# display_driver.net
KiCad netlist of a schematic drawn in EAGLE
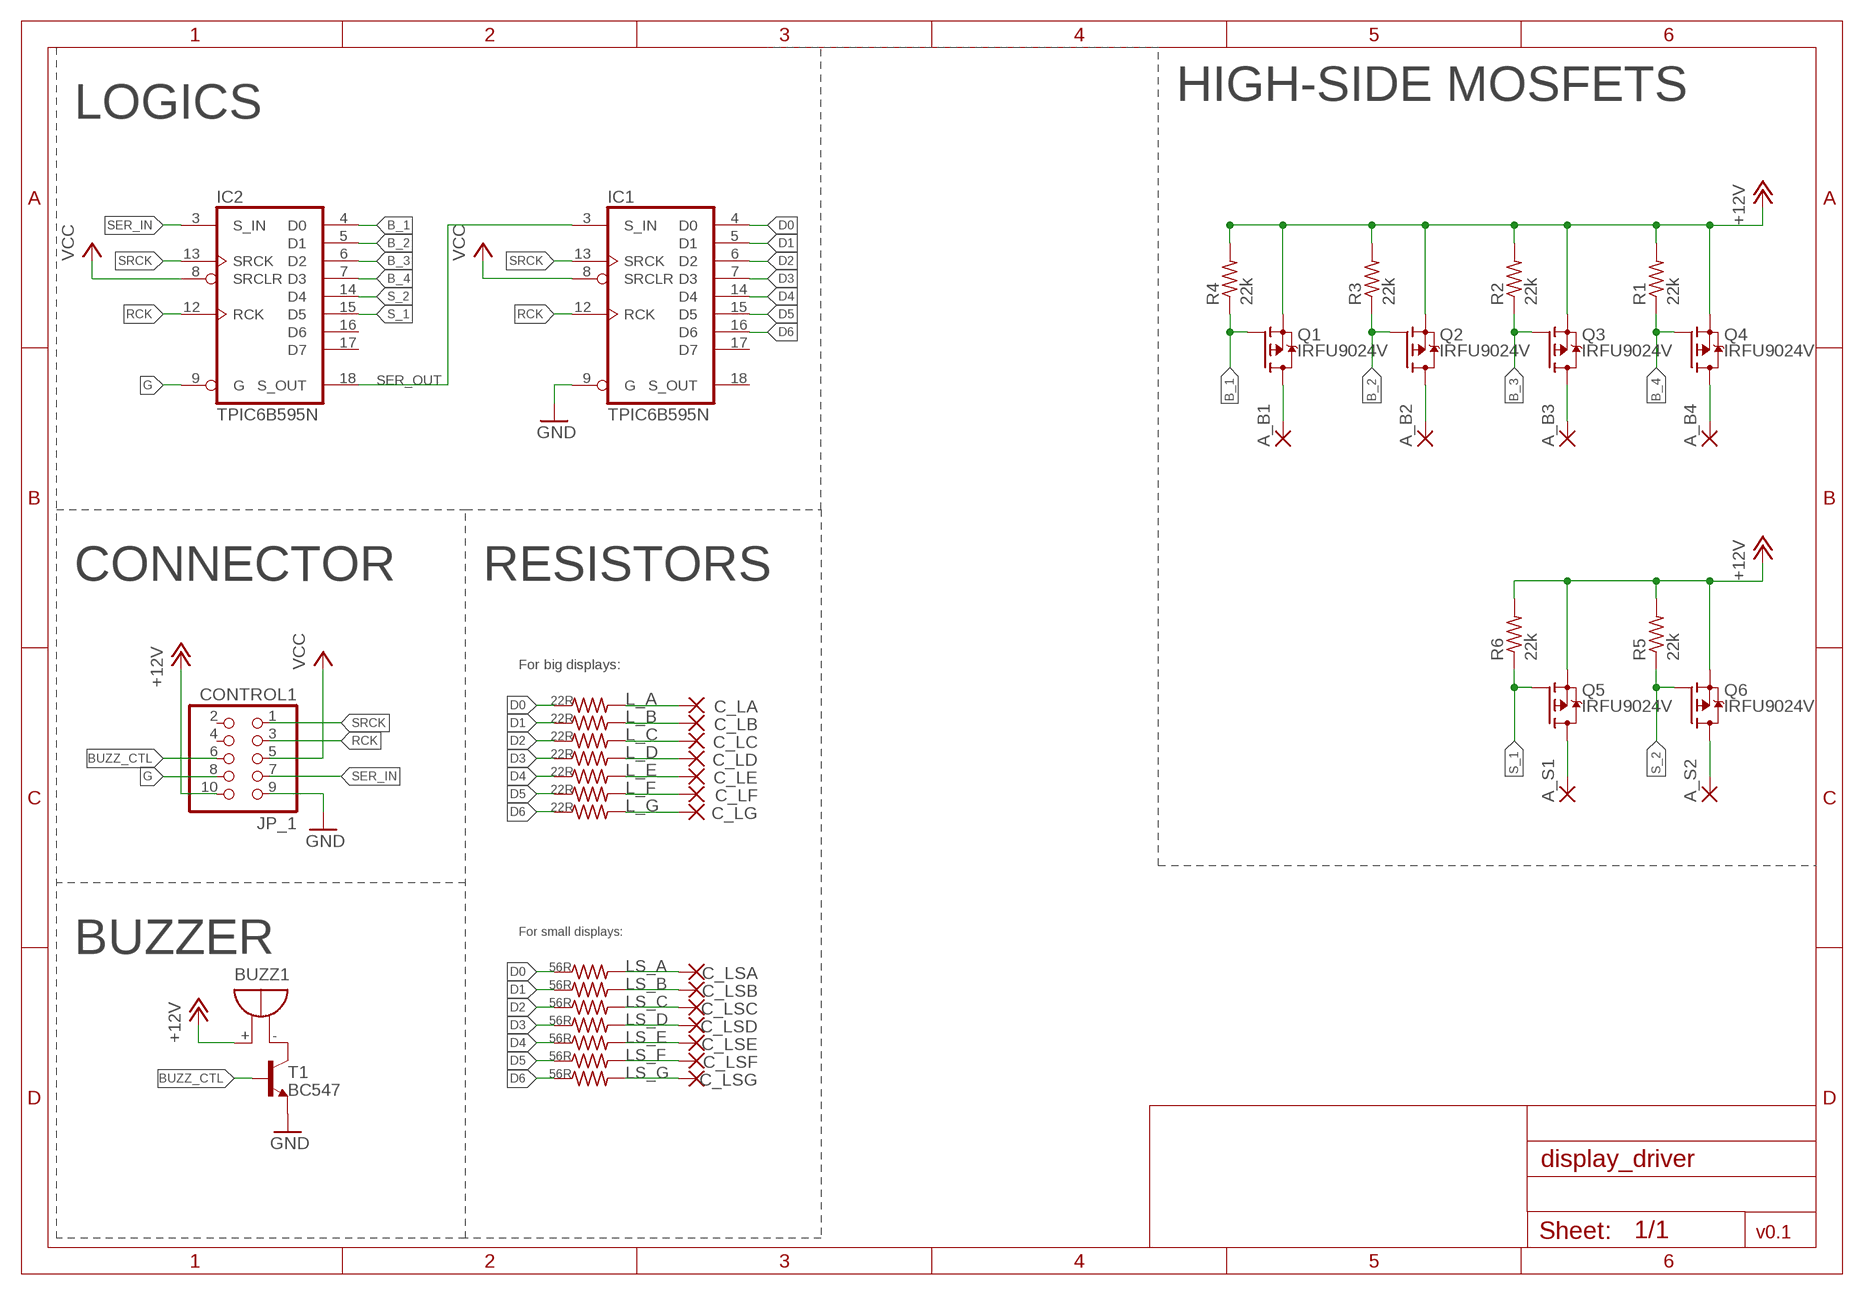
[diagram p0: schematic, sheet 1]

(export (version "E")
  (design (tool "Eeschema 10.0.6"))
  (components
    (comp (ref "A_B1")
      (value "1,6/0,9")
      (footprint "eagle-import:1,6_0,9")
      (libsource (lib "eagle-import") (part "1,6/0,9"))
    )
    (comp (ref "A_B2")
      (value "1,6/0,9")
      (footprint "eagle-import:1,6_0,9")
      (libsource (lib "eagle-import") (part "1,6/0,9"))
    )
    (comp (ref "A_B3")
      (value "1,6/0,9")
      (footprint "eagle-import:1,6_0,9")
      (libsource (lib "eagle-import") (part "1,6/0,9"))
    )
    (comp (ref "A_B4")
      (value "1,6/0,9")
      (footprint "eagle-import:1,6_0,9")
      (libsource (lib "eagle-import") (part "1,6/0,9"))
    )
    (comp (ref "A_S1")
      (value "1,6/0,9")
      (footprint "eagle-import:1,6_0,9")
      (libsource (lib "eagle-import") (part "1,6/0,9"))
    )
    (comp (ref "A_S2")
      (value "1,6/0,9")
      (footprint "eagle-import:1,6_0,9")
      (libsource (lib "eagle-import") (part "1,6/0,9"))
    )
    (comp (ref "BUZZ1")
      (value "F/BC40")
      (footprint "eagle-import:F_BC40")
      (libsource (lib "eagle-import") (part "F/BC40"))
    )
    (comp (ref "CONTROL1")
      (value "JP_1")
      (footprint "eagle-import:2X05")
      (libsource (lib "eagle-import") (part "PINHD-2X5"))
    )
    (comp (ref "C_LA")
      (value "1,6/0,9")
      (footprint "eagle-import:1,6_0,9")
      (libsource (lib "eagle-import") (part "1,6/0,9"))
    )
    (comp (ref "C_LB")
      (value "1,6/0,9")
      (footprint "eagle-import:1,6_0,9")
      (libsource (lib "eagle-import") (part "1,6/0,9"))
    )
    (comp (ref "C_LC")
      (value "1,6/0,9")
      (footprint "eagle-import:1,6_0,9")
      (libsource (lib "eagle-import") (part "1,6/0,9"))
    )
    (comp (ref "C_LD")
      (value "1,6/0,9")
      (footprint "eagle-import:1,6_0,9")
      (libsource (lib "eagle-import") (part "1,6/0,9"))
    )
    (comp (ref "C_LE")
      (value "1,6/0,9")
      (footprint "eagle-import:1,6_0,9")
      (libsource (lib "eagle-import") (part "1,6/0,9"))
    )
    (comp (ref "C_LF")
      (value "1,6/0,9")
      (footprint "eagle-import:1,6_0,9")
      (libsource (lib "eagle-import") (part "1,6/0,9"))
    )
    (comp (ref "C_LG")
      (value "1,6/0,9")
      (footprint "eagle-import:1,6_0,9")
      (libsource (lib "eagle-import") (part "1,6/0,9"))
    )
    (comp (ref "C_LSA")
      (value "1,6/0,9")
      (footprint "eagle-import:1,6_0,9")
      (libsource (lib "eagle-import") (part "1,6/0,9"))
    )
    (comp (ref "C_LSB")
      (value "1,6/0,9")
      (footprint "eagle-import:1,6_0,9")
      (libsource (lib "eagle-import") (part "1,6/0,9"))
    )
    (comp (ref "C_LSC")
      (value "1,6/0,9")
      (footprint "eagle-import:1,6_0,9")
      (libsource (lib "eagle-import") (part "1,6/0,9"))
    )
    (comp (ref "C_LSD")
      (value "1,6/0,9")
      (footprint "eagle-import:1,6_0,9")
      (libsource (lib "eagle-import") (part "1,6/0,9"))
    )
    (comp (ref "C_LSE")
      (value "1,6/0,9")
      (footprint "eagle-import:1,6_0,9")
      (libsource (lib "eagle-import") (part "1,6/0,9"))
    )
    (comp (ref "C_LSF")
      (value "1,6/0,9")
      (footprint "eagle-import:1,6_0,9")
      (libsource (lib "eagle-import") (part "1,6/0,9"))
    )
    (comp (ref "C_LSG")
      (value "1,6/0,9")
      (footprint "eagle-import:1,6_0,9")
      (libsource (lib "eagle-import") (part "1,6/0,9"))
    )
    (comp (ref "IC1")
      (value "TPIC6B595N")
      (footprint "eagle-import:DIL20")
      (libsource (lib "eagle-import") (part "TPIC6B595N"))
    )
    (comp (ref "IC2")
      (value "TPIC6B595N")
      (footprint "eagle-import:DIL20")
      (libsource (lib "eagle-import") (part "TPIC6B595N"))
    )
    (comp (ref "Q1")
      (value "IRFU9024V")
      (footprint "eagle-import:TO251AA-V")
      (libsource (lib "eagle-import") (part "IRFU9024V"))
    )
    (comp (ref "Q2")
      (value "IRFU9024V")
      (footprint "eagle-import:TO251AA-V")
      (libsource (lib "eagle-import") (part "IRFU9024V"))
    )
    (comp (ref "Q3")
      (value "IRFU9024V")
      (footprint "eagle-import:TO251AA-V")
      (libsource (lib "eagle-import") (part "IRFU9024V"))
    )
    (comp (ref "Q4")
      (value "IRFU9024V")
      (footprint "eagle-import:TO251AA-V")
      (libsource (lib "eagle-import") (part "IRFU9024V"))
    )
    (comp (ref "Q5")
      (value "IRFU9024V")
      (footprint "eagle-import:TO251AA-V")
      (libsource (lib "eagle-import") (part "IRFU9024V"))
    )
    (comp (ref "Q6")
      (value "IRFU9024V")
      (footprint "eagle-import:TO251AA-V")
      (libsource (lib "eagle-import") (part "IRFU9024V"))
    )
    (comp (ref "R1")
      (value "22k")
      (footprint "eagle-import:0204_5")
      (libsource (lib "eagle-import") (part "R-US_0204/5"))
    )
    (comp (ref "R2")
      (value "22k")
      (footprint "eagle-import:0204_5")
      (libsource (lib "eagle-import") (part "R-US_0204/5"))
    )
    (comp (ref "R3")
      (value "22k")
      (footprint "eagle-import:0204_5")
      (libsource (lib "eagle-import") (part "R-US_0204/5"))
    )
    (comp (ref "R4")
      (value "22k")
      (footprint "eagle-import:0204_5")
      (libsource (lib "eagle-import") (part "R-US_0204/5"))
    )
    (comp (ref "R5")
      (value "22k")
      (footprint "eagle-import:0204_5")
      (libsource (lib "eagle-import") (part "R-US_0204/5"))
    )
    (comp (ref "R6")
      (value "22k")
      (footprint "eagle-import:0204_5")
      (libsource (lib "eagle-import") (part "R-US_0204/5"))
    )
    (comp (ref "R7")
      (value "22R")
      (footprint "eagle-import:0207_12")
      (libsource (lib "eagle-import") (part "R-US_0207/12"))
    )
    (comp (ref "R8")
      (value "22R")
      (footprint "eagle-import:0207_12")
      (libsource (lib "eagle-import") (part "R-US_0207/12"))
    )
    (comp (ref "R9")
      (value "22R")
      (footprint "eagle-import:0207_12")
      (libsource (lib "eagle-import") (part "R-US_0207/12"))
    )
    (comp (ref "R10")
      (value "22R")
      (footprint "eagle-import:0207_12")
      (libsource (lib "eagle-import") (part "R-US_0207/12"))
    )
    (comp (ref "R11")
      (value "22R")
      (footprint "eagle-import:0207_12")
      (libsource (lib "eagle-import") (part "R-US_0207/12"))
    )
    (comp (ref "R12")
      (value "22R")
      (footprint "eagle-import:0207_12")
      (libsource (lib "eagle-import") (part "R-US_0207/12"))
    )
    (comp (ref "R13")
      (value "22R")
      (footprint "eagle-import:0207_12")
      (libsource (lib "eagle-import") (part "R-US_0207/12"))
    )
    (comp (ref "R14")
      (value "56R")
      (footprint "eagle-import:0207_10")
      (libsource (lib "eagle-import") (part "R-US_0207/10"))
    )
    (comp (ref "R15")
      (value "56R")
      (footprint "eagle-import:0207_10")
      (libsource (lib "eagle-import") (part "R-US_0207/10"))
    )
    (comp (ref "R16")
      (value "56R")
      (footprint "eagle-import:0207_10")
      (libsource (lib "eagle-import") (part "R-US_0207/10"))
    )
    (comp (ref "R17")
      (value "56R")
      (footprint "eagle-import:0207_10")
      (libsource (lib "eagle-import") (part "R-US_0207/10"))
    )
    (comp (ref "R18")
      (value "56R")
      (footprint "eagle-import:0207_10")
      (libsource (lib "eagle-import") (part "R-US_0207/10"))
    )
    (comp (ref "R19")
      (value "56R")
      (footprint "eagle-import:0207_10")
      (libsource (lib "eagle-import") (part "R-US_0207/10"))
    )
    (comp (ref "R20")
      (value "56R")
      (footprint "eagle-import:0207_10")
      (libsource (lib "eagle-import") (part "R-US_0207/10"))
    )
    (comp (ref "T1")
      (value "BC547")
      (footprint "eagle-import:TO92")
      (libsource (lib "eagle-import") (part "BC547"))
    )
  )
  (nets
    (net (code "1") (name "+12V") (class "Default")
      (node (ref "BUZZ1") (pin "+") (pinfunction "+_+") (pintype "passive"))
      (node (ref "CONTROL1") (pin "10") (pinfunction "10_10") (pintype "passive"))
      (node (ref "Q1") (pin "3") (pinfunction "S_3") (pintype "passive"))
      (node (ref "Q2") (pin "3") (pinfunction "S_3") (pintype "passive"))
      (node (ref "Q3") (pin "3") (pinfunction "S_3") (pintype "passive"))
      (node (ref "Q4") (pin "3") (pinfunction "S_3") (pintype "passive"))
      (node (ref "Q5") (pin "3") (pinfunction "S_3") (pintype "passive"))
      (node (ref "Q6") (pin "3") (pinfunction "S_3") (pintype "passive"))
      (node (ref "R1") (pin "2") (pinfunction "2_2") (pintype "passive"))
      (node (ref "R2") (pin "2") (pinfunction "2_2") (pintype "passive"))
      (node (ref "R3") (pin "2") (pinfunction "2_2") (pintype "passive"))
      (node (ref "R4") (pin "2") (pinfunction "2_2") (pintype "passive"))
      (node (ref "R5") (pin "2") (pinfunction "2_2") (pintype "passive"))
      (node (ref "R6") (pin "2") (pinfunction "2_2") (pintype "passive"))
    )
    (net (code "2") (name "/LS_A") (class "Default")
      (node (ref "C_LSA") (pin "1") (pinfunction "P_1") (pintype "passive"))
      (node (ref "R14") (pin "2") (pinfunction "2_2") (pintype "passive"))
    )
    (net (code "3") (name "/LS_B") (class "Default")
      (node (ref "C_LSB") (pin "1") (pinfunction "P_1") (pintype "passive"))
      (node (ref "R15") (pin "2") (pinfunction "2_2") (pintype "passive"))
    )
    (net (code "4") (name "/LS_C") (class "Default")
      (node (ref "C_LSC") (pin "1") (pinfunction "P_1") (pintype "passive"))
      (node (ref "R16") (pin "2") (pinfunction "2_2") (pintype "passive"))
    )
    (net (code "5") (name "/LS_D") (class "Default")
      (node (ref "C_LSD") (pin "1") (pinfunction "P_1") (pintype "passive"))
      (node (ref "R17") (pin "2") (pinfunction "2_2") (pintype "passive"))
    )
    (net (code "6") (name "/LS_E") (class "Default")
      (node (ref "C_LSE") (pin "1") (pinfunction "P_1") (pintype "passive"))
      (node (ref "R18") (pin "2") (pinfunction "2_2") (pintype "passive"))
    )
    (net (code "7") (name "/LS_F") (class "Default")
      (node (ref "C_LSF") (pin "1") (pinfunction "P_1") (pintype "passive"))
      (node (ref "R19") (pin "2") (pinfunction "2_2") (pintype "passive"))
    )
    (net (code "8") (name "/LS_G") (class "Default")
      (node (ref "C_LSG") (pin "1") (pinfunction "P_1") (pintype "passive"))
      (node (ref "R20") (pin "2") (pinfunction "2_2") (pintype "passive"))
    )
    (net (code "9") (name "/L_A") (class "Default")
      (node (ref "C_LA") (pin "1") (pinfunction "P_1") (pintype "passive"))
      (node (ref "R7") (pin "2") (pinfunction "2_2") (pintype "passive"))
    )
    (net (code "10") (name "/L_B") (class "Default")
      (node (ref "C_LB") (pin "1") (pinfunction "P_1") (pintype "passive"))
      (node (ref "R8") (pin "2") (pinfunction "2_2") (pintype "passive"))
    )
    (net (code "11") (name "/L_C") (class "Default")
      (node (ref "C_LC") (pin "1") (pinfunction "P_1") (pintype "passive"))
      (node (ref "R9") (pin "2") (pinfunction "2_2") (pintype "passive"))
    )
    (net (code "12") (name "/L_D") (class "Default")
      (node (ref "C_LD") (pin "1") (pinfunction "P_1") (pintype "passive"))
      (node (ref "R10") (pin "2") (pinfunction "2_2") (pintype "passive"))
    )
    (net (code "13") (name "/L_E") (class "Default")
      (node (ref "C_LE") (pin "1") (pinfunction "P_1") (pintype "passive"))
      (node (ref "R11") (pin "2") (pinfunction "2_2") (pintype "passive"))
    )
    (net (code "14") (name "/L_F") (class "Default")
      (node (ref "C_LF") (pin "1") (pinfunction "P_1") (pintype "passive"))
      (node (ref "R12") (pin "2") (pinfunction "2_2") (pintype "passive"))
    )
    (net (code "15") (name "/L_G") (class "Default")
      (node (ref "C_LG") (pin "1") (pinfunction "P_1") (pintype "passive"))
      (node (ref "R13") (pin "2") (pinfunction "2_2") (pintype "passive"))
    )
    (net (code "16") (name "/SER_OUT") (class "Default")
      (node (ref "IC1") (pin "3") (pinfunction "S_IN_3") (pintype "input"))
      (node (ref "IC2") (pin "18") (pinfunction "S_OUT_18") (pintype "tri_state"))
    )
    (net (code "17") (name "BUZZ_CTL") (class "Default")
      (node (ref "CONTROL1") (pin "6") (pinfunction "6_6") (pintype "passive"))
      (node (ref "T1") (pin "2") (pinfunction "B_2") (pintype "passive"))
    )
    (net (code "18") (name "B_1") (class "Default")
      (node (ref "IC2") (pin "4") (pinfunction "D0_4") (pintype "tri_state"))
      (node (ref "Q1") (pin "1") (pinfunction "G_1") (pintype "passive"))
      (node (ref "R4") (pin "1") (pinfunction "1_1") (pintype "passive"))
    )
    (net (code "19") (name "B_2") (class "Default")
      (node (ref "IC2") (pin "5") (pinfunction "D1_5") (pintype "tri_state"))
      (node (ref "Q2") (pin "1") (pinfunction "G_1") (pintype "passive"))
      (node (ref "R3") (pin "1") (pinfunction "1_1") (pintype "passive"))
    )
    (net (code "20") (name "B_3") (class "Default")
      (node (ref "IC2") (pin "6") (pinfunction "D2_6") (pintype "tri_state"))
      (node (ref "Q3") (pin "1") (pinfunction "G_1") (pintype "passive"))
      (node (ref "R2") (pin "1") (pinfunction "1_1") (pintype "passive"))
    )
    (net (code "21") (name "B_4") (class "Default")
      (node (ref "IC2") (pin "7") (pinfunction "D3_7") (pintype "tri_state"))
      (node (ref "Q4") (pin "1") (pinfunction "G_1") (pintype "passive"))
      (node (ref "R1") (pin "1") (pinfunction "1_1") (pintype "passive"))
    )
    (net (code "22") (name "D0") (class "Default")
      (node (ref "IC1") (pin "4") (pinfunction "D0_4") (pintype "tri_state"))
      (node (ref "R14") (pin "1") (pinfunction "1_1") (pintype "passive"))
      (node (ref "R7") (pin "1") (pinfunction "1_1") (pintype "passive"))
    )
    (net (code "23") (name "D1") (class "Default")
      (node (ref "IC1") (pin "5") (pinfunction "D1_5") (pintype "tri_state"))
      (node (ref "R15") (pin "1") (pinfunction "1_1") (pintype "passive"))
      (node (ref "R8") (pin "1") (pinfunction "1_1") (pintype "passive"))
    )
    (net (code "24") (name "D2") (class "Default")
      (node (ref "IC1") (pin "6") (pinfunction "D2_6") (pintype "tri_state"))
      (node (ref "R16") (pin "1") (pinfunction "1_1") (pintype "passive"))
      (node (ref "R9") (pin "1") (pinfunction "1_1") (pintype "passive"))
    )
    (net (code "25") (name "D3") (class "Default")
      (node (ref "IC1") (pin "7") (pinfunction "D3_7") (pintype "tri_state"))
      (node (ref "R10") (pin "1") (pinfunction "1_1") (pintype "passive"))
      (node (ref "R17") (pin "1") (pinfunction "1_1") (pintype "passive"))
    )
    (net (code "26") (name "D4") (class "Default")
      (node (ref "IC1") (pin "14") (pinfunction "D4_14") (pintype "tri_state"))
      (node (ref "R11") (pin "1") (pinfunction "1_1") (pintype "passive"))
      (node (ref "R18") (pin "1") (pinfunction "1_1") (pintype "passive"))
    )
    (net (code "27") (name "D5") (class "Default")
      (node (ref "IC1") (pin "15") (pinfunction "D5_15") (pintype "tri_state"))
      (node (ref "R12") (pin "1") (pinfunction "1_1") (pintype "passive"))
      (node (ref "R19") (pin "1") (pinfunction "1_1") (pintype "passive"))
    )
    (net (code "28") (name "D6") (class "Default")
      (node (ref "IC1") (pin "16") (pinfunction "D6_16") (pintype "tri_state"))
      (node (ref "R13") (pin "1") (pinfunction "1_1") (pintype "passive"))
      (node (ref "R20") (pin "1") (pinfunction "1_1") (pintype "passive"))
    )
    (net (code "29") (name "G") (class "Default")
      (node (ref "CONTROL1") (pin "8") (pinfunction "8_8") (pintype "passive"))
      (node (ref "IC2") (pin "9") (pinfunction "G_9") (pintype "input"))
    )
    (net (code "30") (name "GND") (class "Default")
      (node (ref "CONTROL1") (pin "9") (pinfunction "9_9") (pintype "passive"))
      (node (ref "IC1") (pin "9") (pinfunction "G_9") (pintype "input"))
      (node (ref "T1") (pin "1") (pinfunction "E_1") (pintype "passive"))
    )
    (net (code "31") (name "Net-(A_B1-P)") (class "Default")
      (node (ref "A_B1") (pin "1") (pinfunction "P_1") (pintype "passive"))
      (node (ref "Q1") (pin "2") (pinfunction "D_2") (pintype "passive"))
    )
    (net (code "32") (name "Net-(A_B2-P)") (class "Default")
      (node (ref "A_B2") (pin "1") (pinfunction "P_1") (pintype "passive"))
      (node (ref "Q2") (pin "2") (pinfunction "D_2") (pintype "passive"))
    )
    (net (code "33") (name "Net-(A_B3-P)") (class "Default")
      (node (ref "A_B3") (pin "1") (pinfunction "P_1") (pintype "passive"))
      (node (ref "Q3") (pin "2") (pinfunction "D_2") (pintype "passive"))
    )
    (net (code "34") (name "Net-(A_B4-P)") (class "Default")
      (node (ref "A_B4") (pin "1") (pinfunction "P_1") (pintype "passive"))
      (node (ref "Q4") (pin "2") (pinfunction "D_2") (pintype "passive"))
    )
    (net (code "35") (name "Net-(A_S1-P)") (class "Default")
      (node (ref "A_S1") (pin "1") (pinfunction "P_1") (pintype "passive"))
      (node (ref "Q5") (pin "2") (pinfunction "D_2") (pintype "passive"))
    )
    (net (code "36") (name "Net-(A_S2-P)") (class "Default")
      (node (ref "A_S2") (pin "1") (pinfunction "P_1") (pintype "passive"))
      (node (ref "Q6") (pin "2") (pinfunction "D_2") (pintype "passive"))
    )
    (net (code "37") (name "Net-(T1-C)") (class "Default")
      (node (ref "BUZZ1") (pin "-") (pinfunction "-_-") (pintype "passive"))
      (node (ref "T1") (pin "3") (pinfunction "C_3") (pintype "passive"))
    )
    (net (code "38") (name "RCK") (class "Default")
      (node (ref "CONTROL1") (pin "3") (pinfunction "3_3") (pintype "passive"))
      (node (ref "IC1") (pin "12") (pinfunction "RCK_12") (pintype "input"))
      (node (ref "IC2") (pin "12") (pinfunction "RCK_12") (pintype "input"))
    )
    (net (code "39") (name "SER_IN") (class "Default")
      (node (ref "CONTROL1") (pin "7") (pinfunction "7_7") (pintype "passive"))
      (node (ref "IC2") (pin "3") (pinfunction "S_IN_3") (pintype "input"))
    )
    (net (code "40") (name "SRCK") (class "Default")
      (node (ref "CONTROL1") (pin "1") (pinfunction "1_1") (pintype "passive"))
      (node (ref "IC1") (pin "13") (pinfunction "SRCK_13") (pintype "input"))
      (node (ref "IC2") (pin "13") (pinfunction "SRCK_13") (pintype "input"))
    )
    (net (code "41") (name "S_1") (class "Default")
      (node (ref "IC2") (pin "15") (pinfunction "D5_15") (pintype "tri_state"))
      (node (ref "Q5") (pin "1") (pinfunction "G_1") (pintype "passive"))
      (node (ref "R6") (pin "1") (pinfunction "1_1") (pintype "passive"))
    )
    (net (code "42") (name "S_2") (class "Default")
      (node (ref "IC2") (pin "14") (pinfunction "D4_14") (pintype "tri_state"))
      (node (ref "Q6") (pin "1") (pinfunction "G_1") (pintype "passive"))
      (node (ref "R5") (pin "1") (pinfunction "1_1") (pintype "passive"))
    )
    (net (code "43") (name "VCC") (class "Default")
      (node (ref "CONTROL1") (pin "5") (pinfunction "5_5") (pintype "passive"))
      (node (ref "IC1") (pin "8") (pinfunction "SRCLR_8") (pintype "input"))
      (node (ref "IC2") (pin "8") (pinfunction "SRCLR_8") (pintype "input"))
    )
    (net (code "44") (name "unconnected-(CONTROL1-Pad2)") (class "Default")
      (node (ref "CONTROL1") (pin "2") (pinfunction "2_2") (pintype "passive"))
    )
    (net (code "45") (name "unconnected-(CONTROL1-Pad4)") (class "Default")
      (node (ref "CONTROL1") (pin "4") (pinfunction "4_4") (pintype "passive"))
    )
    (net (code "46") (name "unconnected-(IC1A-D7-Pad17)") (class "Default")
      (node (ref "IC1") (pin "17") (pinfunction "D7_17") (pintype "tri_state"))
    )
    (net (code "47") (name "unconnected-(IC1A-S_OUT-Pad18)") (class "Default")
      (node (ref "IC1") (pin "18") (pinfunction "S_OUT_18") (pintype "tri_state"))
    )
    (net (code "48") (name "unconnected-(IC2A-D6-Pad16)") (class "Default")
      (node (ref "IC2") (pin "16") (pinfunction "D6_16") (pintype "tri_state"))
    )
    (net (code "49") (name "unconnected-(IC2A-D7-Pad17)") (class "Default")
      (node (ref "IC2") (pin "17") (pinfunction "D7_17") (pintype "tri_state"))
    )
  )
)
